# M24C02.net
KiCad netlist of a schematic drawn in Altium Designer
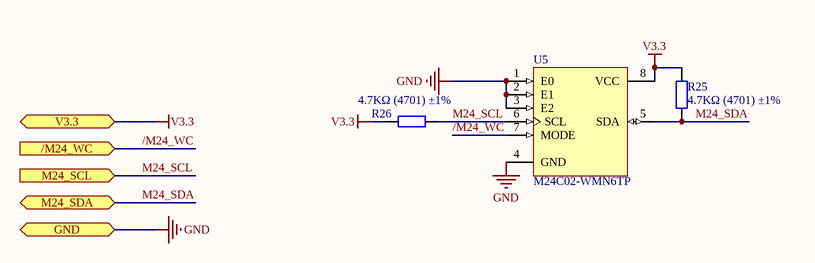
[diagram p0: M24C02.SchDoc]

(export (version "E")
  (design (tool "Eeschema 10.0.6"))
  (components
    (comp (ref "R25")
      (value "4.7KΩ (4701) ±1%")
      (footprint "0805_R")
      (description "贴片电阻")
      (libsource (lib "") (part "0805 4.7KΩ (4701) 1%_1"))
    )
    (comp (ref "R26")
      (value "4.7KΩ (4701) ±1%")
      (footprint "0805_R")
      (description "贴片电阻")
      (libsource (lib "Miscellaneous Devices LC") (part "0805 4.7KΩ (4701) 1%"))
    )
    (comp (ref "U5")
      (value "M24C02-WMN6TP")
      (footprint "SOIC-8_150mil")
      (description "EEPROM")
      (libsource (lib "Miscellaneous Devices LC") (part "M24C02-WMN6TP_[C7562]"))
    )
  )
  (nets
    (net (code "1") (name "/M24_SCL") (class "Default")
      (node (ref "R26") (pin "1") (pinfunction "1_1") (pintype "passive"))
      (node (ref "U5") (pin "6") (pinfunction "SCL_6") (pintype "input"))
    )
    (net (code "2") (name "/M24_SDA") (class "Default")
      (node (ref "R25") (pin "1") (pinfunction "1_1") (pintype "passive"))
      (node (ref "U5") (pin "5") (pinfunction "SDA_5") (pintype "bidirectional"))
    )
    (net (code "3") (name "/{slash}M24_WC") (class "Default")
      (node (ref "U5") (pin "7") (pinfunction "MODE_7") (pintype "input"))
    )
    (net (code "4") (name "GND") (class "Default")
      (node (ref "U5") (pin "1") (pinfunction "E0_1") (pintype "input"))
      (node (ref "U5") (pin "2") (pinfunction "E1_2") (pintype "input"))
      (node (ref "U5") (pin "3") (pinfunction "E2_3") (pintype "input"))
      (node (ref "U5") (pin "4") (pinfunction "GND_4") (pintype "power_in"))
    )
    (net (code "5") (name "V3.3") (class "Default")
      (node (ref "R25") (pin "2") (pinfunction "2_2") (pintype "passive"))
      (node (ref "R26") (pin "2") (pinfunction "2_2") (pintype "passive"))
      (node (ref "U5") (pin "8") (pinfunction "VCC_8") (pintype "power_in"))
    )
  )
)
